# blinkm2neo_5Jul2020_qfn.net
KiCad netlist of a schematic drawn in EAGLE
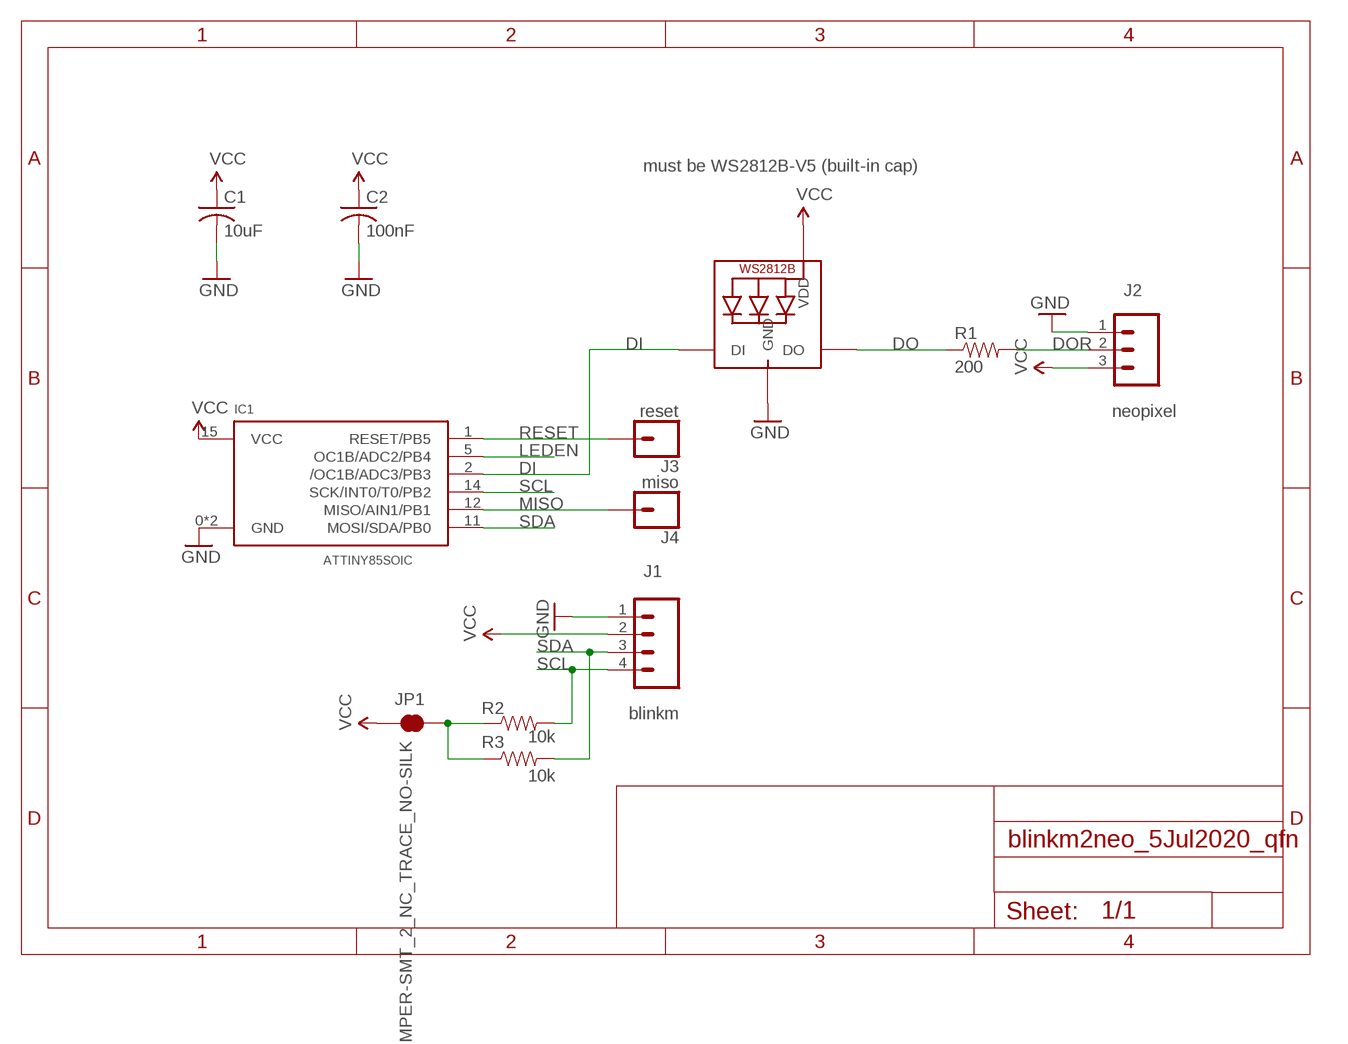
[diagram p0: schematic, sheet 1]

(export (version "E")
  (design (tool "Eeschema 10.0.6"))
  (components
    (comp (ref "C1")
      (value "10uF")
      (footprint "eagle-import:C0402")
      (libsource (lib "eagle-import") (part "C-USC0402"))
    )
    (comp (ref "C2")
      (value "100nF")
      (footprint "eagle-import:C0402")
      (libsource (lib "eagle-import") (part "C-USC0402"))
    )
    (comp (ref "IC1")
      (value "ATTINY85SOIC")
      (footprint "eagle-import:QFN20")
      (libsource (lib "eagle-import") (part "ATTINY45QFN"))
    )
    (comp (ref "J1")
      (value "blinkm")
      (footprint "eagle-import:1X04")
      (libsource (lib "eagle-import") (part "CONN_04"))
    )
    (comp (ref "J2")
      (value "neopixel")
      (footprint "eagle-import:1X03")
      (libsource (lib "eagle-import") (part "CONN_03"))
    )
    (comp (ref "J3")
      (value "reset")
      (footprint "eagle-import:1X01_NO_SILK")
      (libsource (lib "eagle-import") (part "CONN_01PTH_NO_SILK_YES_STOP"))
    )
    (comp (ref "J4")
      (value "miso")
      (footprint "eagle-import:1X01_NO_SILK")
      (libsource (lib "eagle-import") (part "CONN_01PTH_NO_SILK_YES_STOP"))
    )
    (comp (ref "JP1")
      (value "JUMPER-SMT_2_NC_TRACE_NO-SILK")
      (footprint "eagle-import:SMT-JUMPER_2_NC_TRACE_NO-SILK")
      (libsource (lib "eagle-import") (part "JUMPER-SMT_2_NC_TRACE_NO-SILK"))
    )
    (comp (ref "LED1")
      (value "WS2812B-V5")
      (footprint "eagle-import:WS2812B")
      (libsource (lib "eagle-import") (part "WS2812B5050"))
    )
    (comp (ref "R1")
      (value "200")
      (footprint "eagle-import:0402")
      (libsource (lib "eagle-import") (part "RESISTOR0402"))
    )
    (comp (ref "R2")
      (value "10k")
      (footprint "eagle-import:0402")
      (libsource (lib "eagle-import") (part "RESISTOR0402"))
    )
    (comp (ref "R3")
      (value "10k")
      (footprint "eagle-import:0402")
      (libsource (lib "eagle-import") (part "RESISTOR0402"))
    )
  )
  (nets
    (net (code "1") (name "/DI") (class "Default")
      (node (ref "IC1") (pin "2") (pinfunction "/OC1B/ADC3/PB3_2") (pintype "bidirectional"))
      (node (ref "LED1") (pin "4-DIN") (pinfunction "DI_4-DIN") (pintype "input"))
    )
    (net (code "2") (name "/DO") (class "Default")
      (node (ref "LED1") (pin "2-DOUT") (pinfunction "DO_2-DOUT") (pintype "output"))
      (node (ref "R1") (pin "1") (pinfunction "1_1") (pintype "passive"))
    )
    (net (code "3") (name "/DOR") (class "Default")
      (node (ref "J2") (pin "2") (pinfunction "2_2") (pintype "passive"))
      (node (ref "R1") (pin "2") (pinfunction "2_2") (pintype "passive"))
    )
    (net (code "4") (name "/LEDEN") (class "Default")
      (node (ref "IC1") (pin "5") (pinfunction "OC1B/ADC2/PB4_5") (pintype "bidirectional"))
    )
    (net (code "5") (name "/MISO") (class "Default")
      (node (ref "IC1") (pin "12") (pinfunction "MISO/AIN1/PB1_12") (pintype "bidirectional"))
      (node (ref "J4") (pin "1") (pinfunction "1_1") (pintype "passive"))
    )
    (net (code "6") (name "/RESET") (class "Default")
      (node (ref "IC1") (pin "1") (pinfunction "RESET/PB5_1") (pintype "bidirectional"))
      (node (ref "J3") (pin "1") (pinfunction "1_1") (pintype "passive"))
    )
    (net (code "7") (name "/SCL") (class "Default")
      (node (ref "IC1") (pin "14") (pinfunction "SCK/INT0/T0/PB2_14") (pintype "bidirectional"))
      (node (ref "J1") (pin "4") (pinfunction "4_4") (pintype "passive"))
      (node (ref "R2") (pin "2") (pinfunction "2_2") (pintype "passive"))
    )
    (net (code "8") (name "/SDA") (class "Default")
      (node (ref "IC1") (pin "11") (pinfunction "MOSI/SDA/PB0_11") (pintype "bidirectional"))
      (node (ref "J1") (pin "3") (pinfunction "3_3") (pintype "passive"))
      (node (ref "R3") (pin "2") (pinfunction "2_2") (pintype "passive"))
    )
    (net (code "9") (name "GND") (class "Default")
      (node (ref "C1") (pin "2") (pinfunction "2_2") (pintype "passive"))
      (node (ref "C2") (pin "2") (pinfunction "2_2") (pintype "passive"))
      (node (ref "IC1") (pin "0") (pinfunction "GND_0") (pintype "bidirectional"))
      (node (ref "IC1") (pin "8") (pinfunction "GND_8") (pintype "bidirectional"))
      (node (ref "J1") (pin "1") (pinfunction "1_1") (pintype "passive"))
      (node (ref "J2") (pin "1") (pinfunction "1_1") (pintype "passive"))
      (node (ref "LED1") (pin "3-GND") (pinfunction "GND_3-GND") (pintype "power_in"))
    )
    (net (code "10") (name "Net-(JP1-Pad2)") (class "Default")
      (node (ref "JP1") (pin "2") (pinfunction "2_2") (pintype "passive"))
      (node (ref "R2") (pin "1") (pinfunction "1_1") (pintype "passive"))
      (node (ref "R3") (pin "1") (pinfunction "1_1") (pintype "passive"))
    )
    (net (code "11") (name "VCC") (class "Default")
      (node (ref "C1") (pin "1") (pinfunction "1_1") (pintype "passive"))
      (node (ref "C2") (pin "1") (pinfunction "1_1") (pintype "passive"))
      (node (ref "IC1") (pin "15") (pinfunction "VCC_15") (pintype "bidirectional"))
      (node (ref "J1") (pin "2") (pinfunction "2_2") (pintype "passive"))
      (node (ref "J2") (pin "3") (pinfunction "3_3") (pintype "passive"))
      (node (ref "JP1") (pin "1") (pinfunction "1_1") (pintype "passive"))
      (node (ref "LED1") (pin "1-VDD") (pinfunction "VDD_1-VDD") (pintype "power_in"))
    )
  )
)
